# power_dist.net
KiCad netlist of a schematic drawn in EAGLE
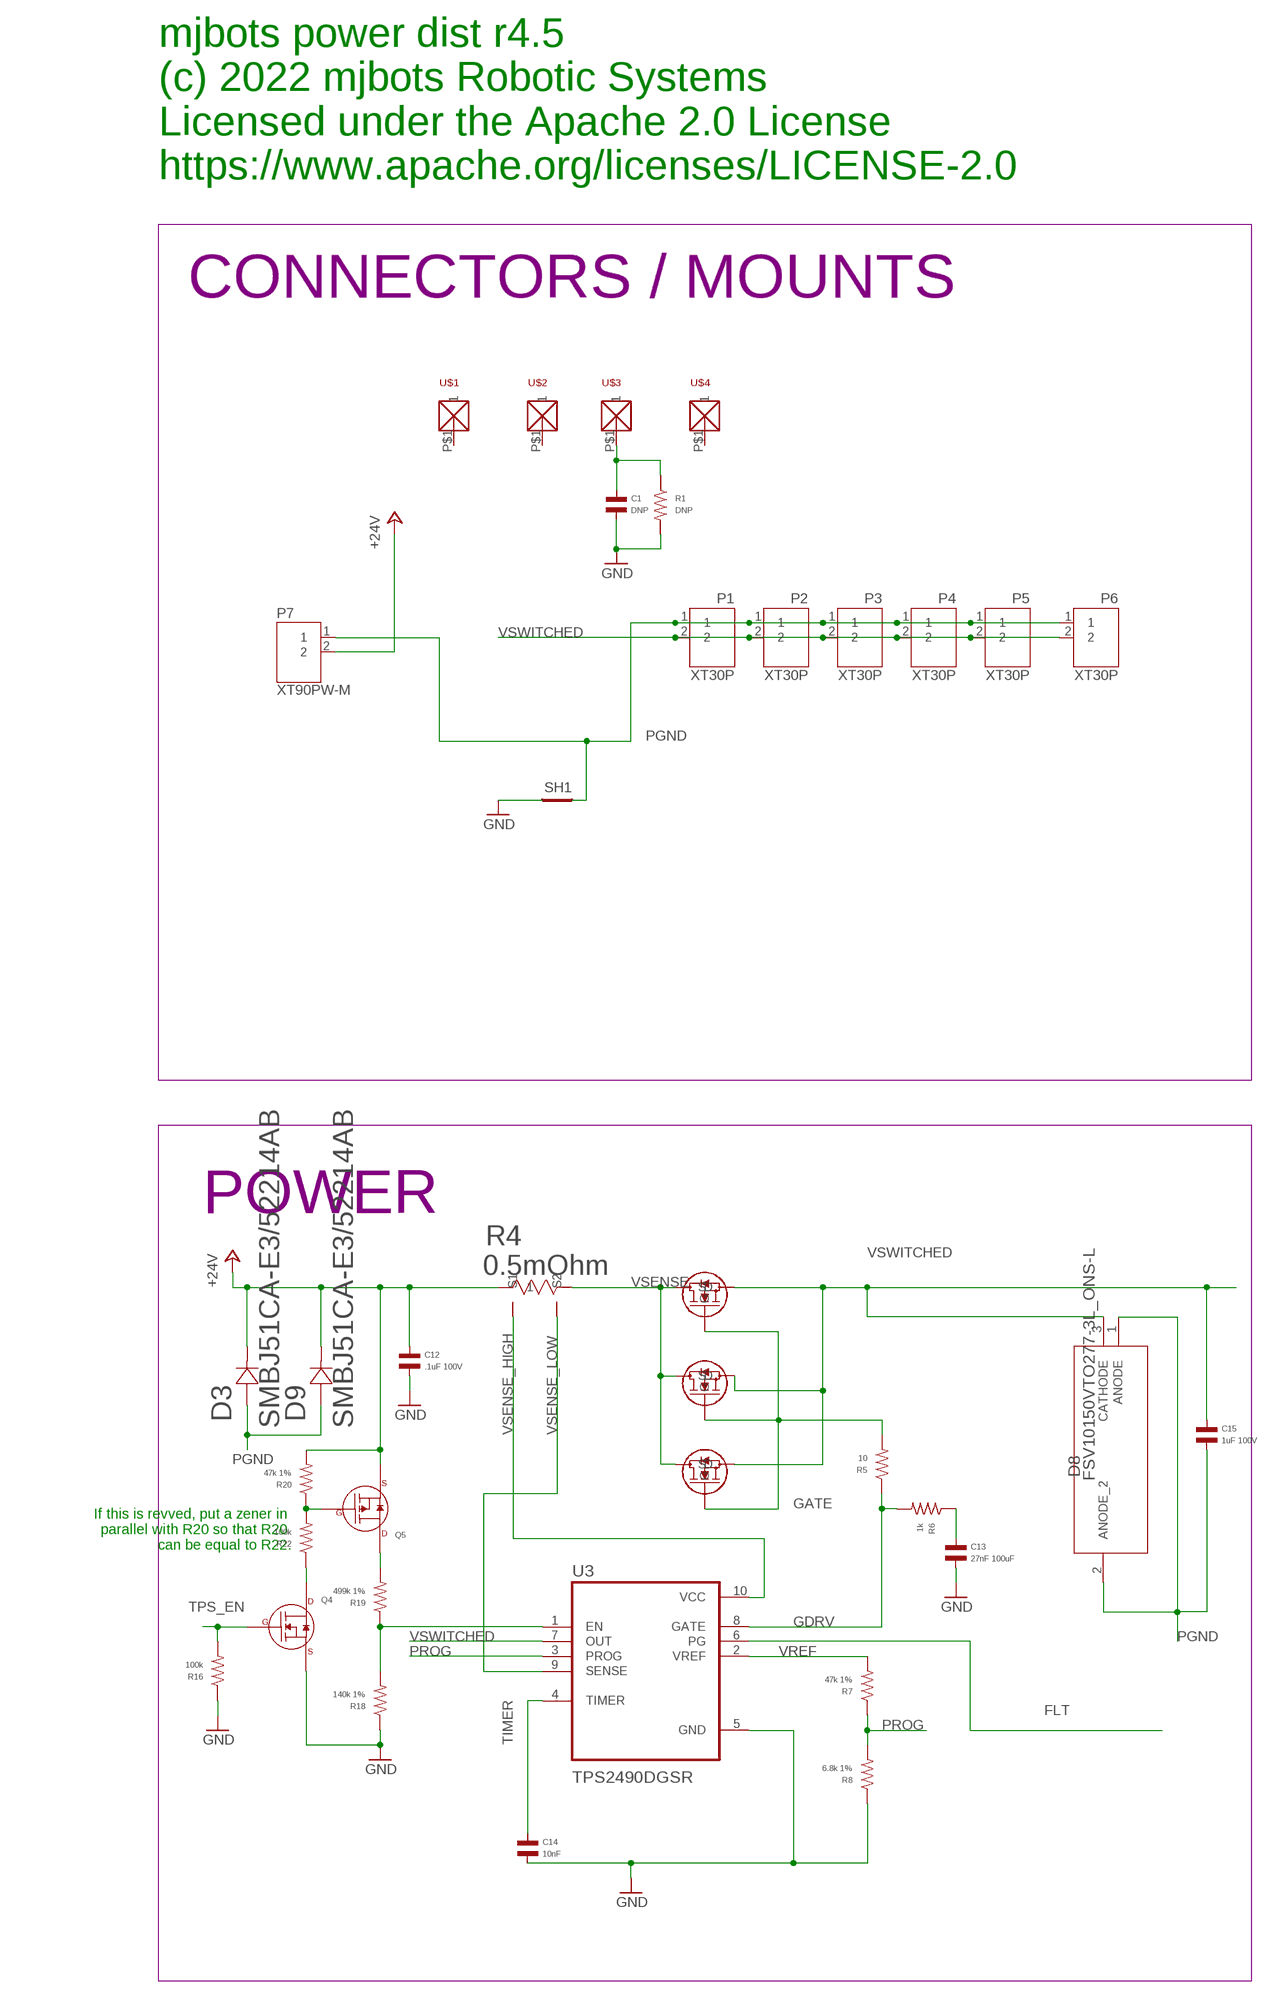
[diagram p0: schematic, sheet 1, part 1 of 2]
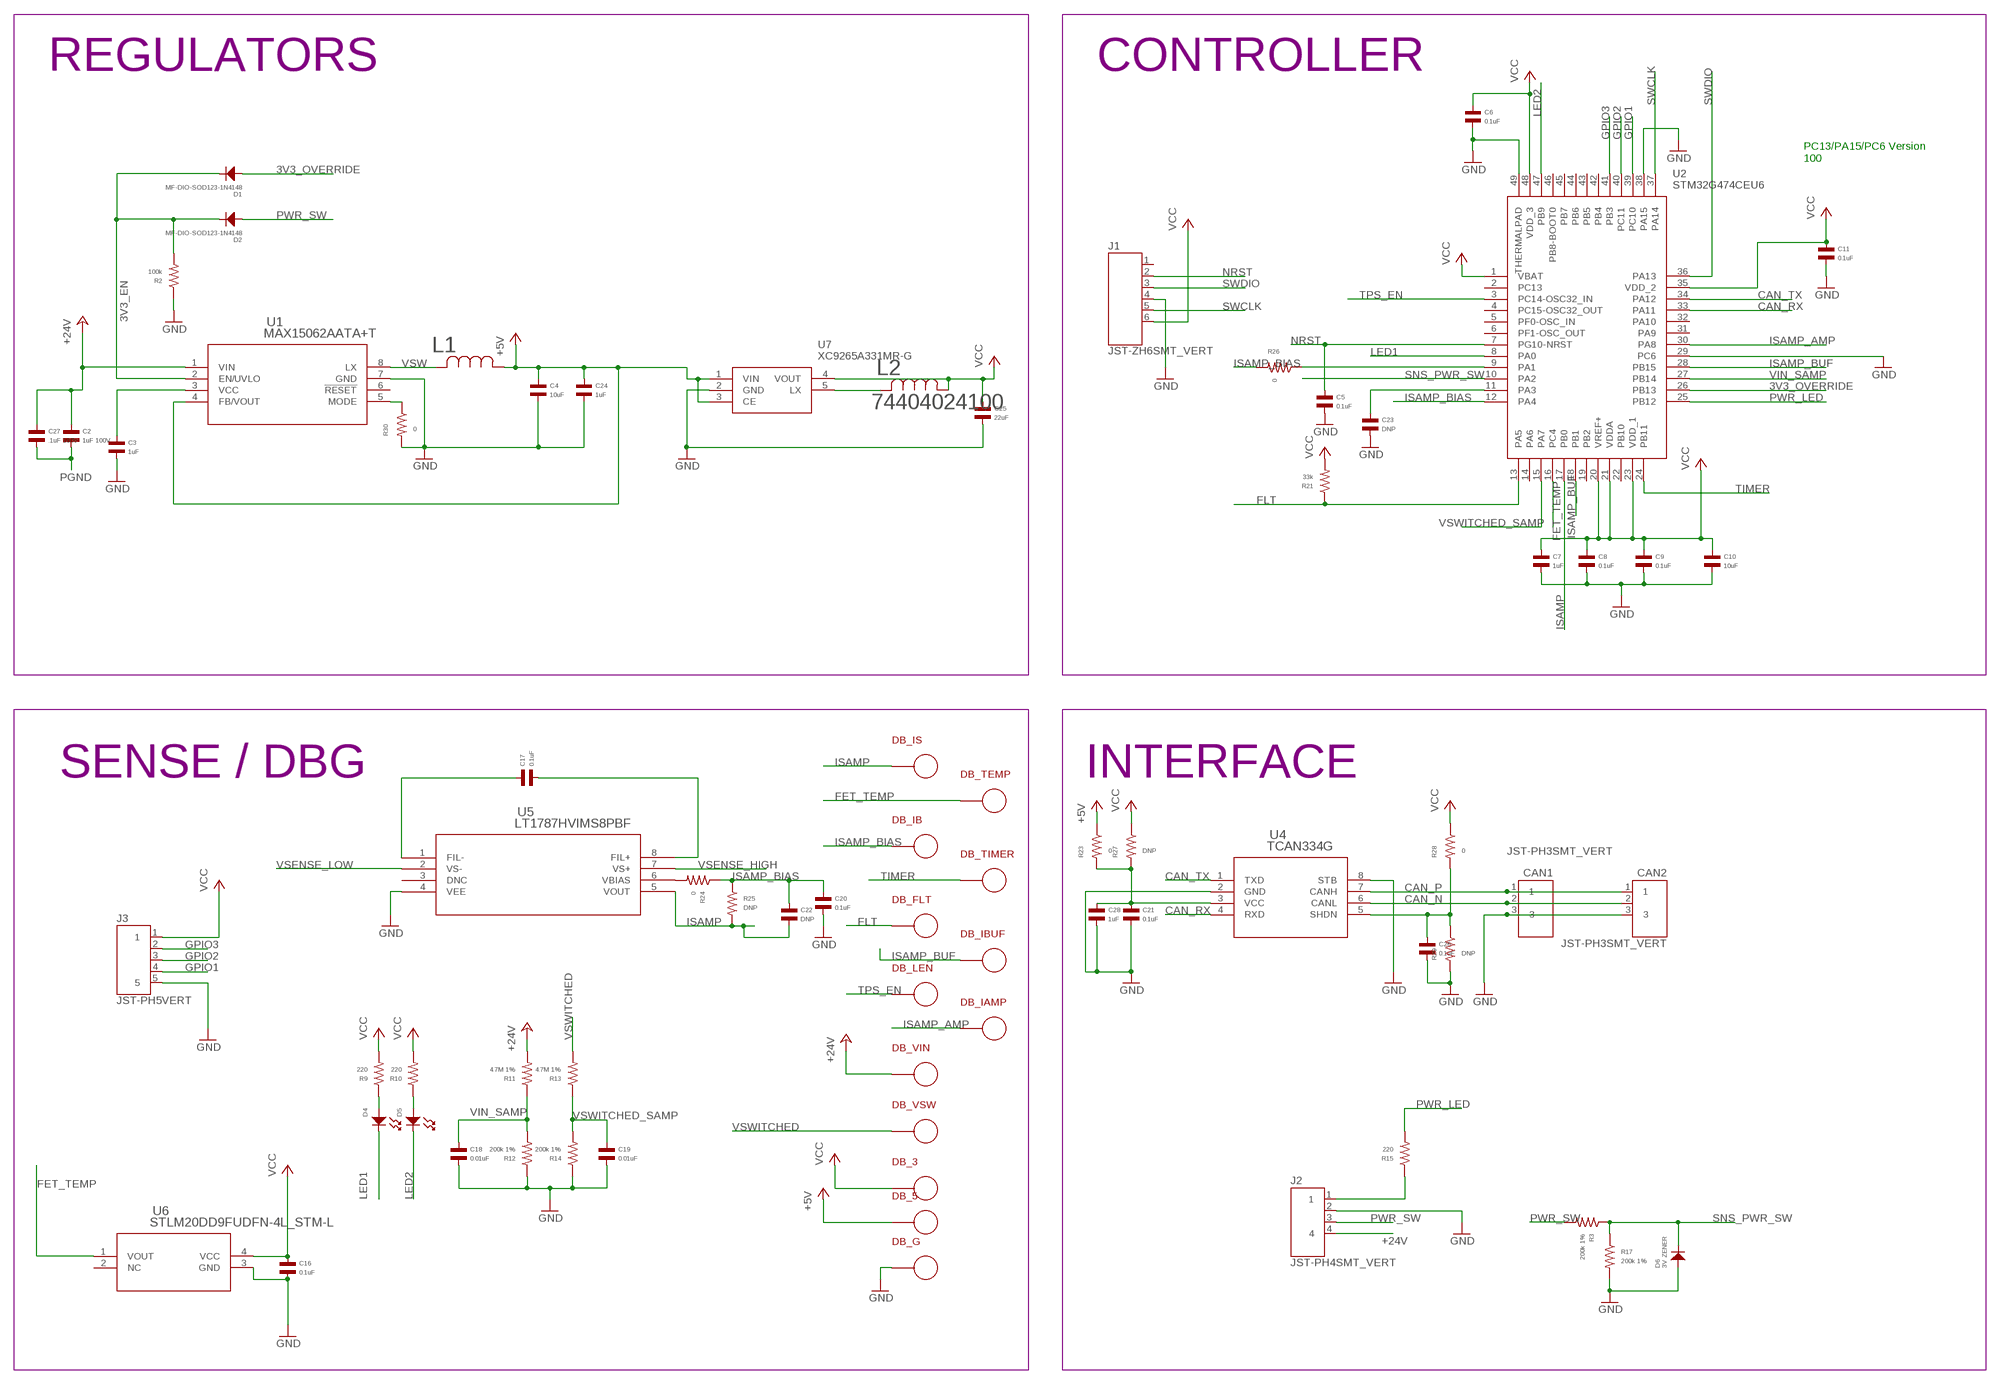
[diagram p1: schematic, sheet 1, part 2 of 2]

(export (version "E")
  (design (tool "Eeschema 10.0.6"))
  (components
    (comp (ref "C1")
      (value "DNP")
      (footprint "eagle-import:C0603")
      (fields (field (name "POPULATE") "0"))
      (libsource (lib "eagle-import") (part "CAPACITOR_NP_0603"))
    )
    (comp (ref "C2")
      (value "1uF 100V")
      (footprint "eagle-import:C0805")
      (fields (field (name "MF") "MURATA") (field (name "MPN") "GCM21BC72A105KE36L"))
      (libsource (lib "eagle-import") (part "CAPACITOR_NP_0805"))
    )
    (comp (ref "C3")
      (value "1uF")
      (footprint "eagle-import:C0603")
      (fields (field (name "HOUSEPART") "1") (field (name "MPN") "MF-CAP-0603-1uF"))
      (libsource (lib "eagle-import") (part "CAPACITOR_NP_0603"))
    )
    (comp (ref "C4")
      (value "10uF")
      (footprint "eagle-import:C1206")
      (fields (field (name "HOUSEPART") "1") (field (name "MPN") "MF-CAP-1206-10uF"))
      (libsource (lib "eagle-import") (part "CAPACITOR_NP_1206"))
    )
    (comp (ref "C5")
      (value "0.1uF")
      (footprint "eagle-import:C0603")
      (fields (field (name "HOUSEPART") "1") (field (name "MPN") "MF-CAP-0603-0.1uF"))
      (libsource (lib "eagle-import") (part "CAPACITOR_NP_0603"))
    )
    (comp (ref "C6")
      (value "0.1uF")
      (footprint "eagle-import:C0603")
      (fields (field (name "HOUSEPART") "1") (field (name "MPN") "MF-CAP-0603-0.1uF"))
      (libsource (lib "eagle-import") (part "CAPACITOR_NP_0603"))
    )
    (comp (ref "C7")
      (value "1uF")
      (footprint "eagle-import:C0603")
      (fields (field (name "HOUSEPART") "1") (field (name "MPN") "MF-CAP-0603-1uF"))
      (libsource (lib "eagle-import") (part "CAPACITOR_NP_0603"))
    )
    (comp (ref "C8")
      (value "0.1uF")
      (footprint "eagle-import:C0603")
      (fields (field (name "HOUSEPART") "1") (field (name "MPN") "MF-CAP-0603-0.1uF"))
      (libsource (lib "eagle-import") (part "CAPACITOR_NP_0603"))
    )
    (comp (ref "C9")
      (value "0.1uF")
      (footprint "eagle-import:C0603")
      (fields (field (name "HOUSEPART") "1") (field (name "MPN") "MF-CAP-0603-0.1uF"))
      (libsource (lib "eagle-import") (part "CAPACITOR_NP_0603"))
    )
    (comp (ref "C10")
      (value "10uF")
      (footprint "eagle-import:C1206")
      (fields (field (name "HOUSEPART") "1") (field (name "MPN") "MF-CAP-1206-10uF"))
      (libsource (lib "eagle-import") (part "CAPACITOR_NP_1206"))
    )
    (comp (ref "C11")
      (value "0.1uF")
      (footprint "eagle-import:C0603")
      (fields (field (name "HOUSEPART") "1") (field (name "MPN") "MF-CAP-0603-0.1uF"))
      (libsource (lib "eagle-import") (part "CAPACITOR_NP_0603"))
    )
    (comp (ref "C12")
      (value ".1uF 100V")
      (footprint "eagle-import:C0603")
      (fields (field (name "HOUSEPART") "0") (field (name "MPN") "GRM188R72A104KA35D"))
      (libsource (lib "eagle-import") (part "CAPACITOR_NP_0603"))
    )
    (comp (ref "C13")
      (value "27nF 100uF")
      (footprint "eagle-import:C0603")
      (fields (field (name "HOUSEPART") "0") (field (name "MPN") "C0603C273K1RAC7867"))
      (libsource (lib "eagle-import") (part "CAPACITOR_NP_0603"))
    )
    (comp (ref "C14")
      (value "10nF")
      (footprint "eagle-import:C0603")
      (fields (field (name "HOUSEPART") "1") (field (name "MPN") "MF-CAP-0603-0.01uF"))
      (libsource (lib "eagle-import") (part "CAPACITOR_NP_0603"))
    )
    (comp (ref "C15")
      (value "1uF 100V")
      (footprint "eagle-import:C0805")
      (fields (field (name "MF") "MURATA") (field (name "MPN") "GCM21BC72A105KE36L"))
      (libsource (lib "eagle-import") (part "CAPACITOR_NP_0805"))
    )
    (comp (ref "C16")
      (value "0.1uF")
      (footprint "eagle-import:C0603")
      (fields (field (name "HOUSEPART") "1") (field (name "MPN") "MF-CAP-0603-0.1uF"))
      (libsource (lib "eagle-import") (part "CAPACITOR_NP_0603"))
    )
    (comp (ref "C17")
      (value "0.1uF")
      (footprint "eagle-import:C0603")
      (fields (field (name "HOUSEPART") "1") (field (name "MPN") "MF-CAP-0603-0.1uF"))
      (libsource (lib "eagle-import") (part "CAPACITOR_NP_0603"))
    )
    (comp (ref "C18")
      (value "0.01uF")
      (footprint "eagle-import:C0603")
      (fields (field (name "HOUSEPART") "1") (field (name "MPN") "MF-CAP-0603-0.01uF"))
      (libsource (lib "eagle-import") (part "CAPACITOR_NP_0603"))
    )
    (comp (ref "C19")
      (value "0.01uF")
      (footprint "eagle-import:C0603")
      (fields (field (name "HOUSEPART") "1") (field (name "MPN") "MF-CAP-0603-0.01uF"))
      (libsource (lib "eagle-import") (part "CAPACITOR_NP_0603"))
    )
    (comp (ref "C20")
      (value "0.1uF")
      (footprint "eagle-import:C0603")
      (fields (field (name "HOUSEPART") "1") (field (name "MPN") "MF-CAP-0603-0.1uF"))
      (libsource (lib "eagle-import") (part "CAPACITOR_NP_0603"))
    )
    (comp (ref "C21")
      (value "0.1uF")
      (footprint "eagle-import:C0603")
      (fields (field (name "HOUSEPART") "1") (field (name "MPN") "MF-CAP-0603-0.1uF"))
      (libsource (lib "eagle-import") (part "CAPACITOR_NP_0603"))
    )
    (comp (ref "C22")
      (value "DNP")
      (footprint "eagle-import:C0603")
      (fields (field (name "HOUSEPART") "1") (field (name "POPULATE") "0"))
      (libsource (lib "eagle-import") (part "CAPACITOR_NP_0603"))
    )
    (comp (ref "C23")
      (value "DNP")
      (footprint "eagle-import:C0603")
      (fields (field (name "HOUSEPART") "1") (field (name "POPULATE") "0"))
      (libsource (lib "eagle-import") (part "CAPACITOR_NP_0603"))
    )
    (comp (ref "C24")
      (value "1uF")
      (footprint "eagle-import:C0402")
      (fields (field (name "HOUSEPART") "1") (field (name "MPN") "MF-CAP-0402-1uF"))
      (libsource (lib "eagle-import") (part "CAPACITOR_NP_0402"))
    )
    (comp (ref "C25")
      (value "22uF")
      (footprint "eagle-import:C1206")
      (fields (field (name "MF") "Samsung") (field (name "MPN") "CL31B226KPHNNNE"))
      (libsource (lib "eagle-import") (part "CAPACITOR_NP_1206"))
    )
    (comp (ref "C26")
      (value "0.1uF")
      (footprint "eagle-import:C0603")
      (fields (field (name "HOUSEPART") "1") (field (name "MPN") "MF-CAP-0603-0.1uF"))
      (libsource (lib "eagle-import") (part "CAPACITOR_NP_0603"))
    )
    (comp (ref "C27")
      (value ".1uF 100V")
      (footprint "eagle-import:C0603")
      (fields (field (name "HOUSEPART") "0") (field (name "MPN") "GRM188R72A104KA35D"))
      (libsource (lib "eagle-import") (part "CAPACITOR_NP_0603"))
    )
    (comp (ref "C28")
      (value "1uF")
      (footprint "eagle-import:C0603")
      (fields (field (name "HOUSEPART") "1") (field (name "MPN") "MF-CAP-0603-1uF"))
      (libsource (lib "eagle-import") (part "CAPACITOR_NP_0603"))
    )
    (comp (ref "CAN1")
      (value "JST-PH3SMT_VERT")
      (footprint "eagle-import:JST_B3B_PH-SM4-TB(LF)(SN)")
      (fields (field (name "MF") "JST") (field (name "MPN") "B3B-PH-SM4-TB(LF)(SN)"))
      (libsource (lib "eagle-import") (part "JST-PH3SMT_VERT"))
    )
    (comp (ref "CAN2")
      (value "JST-PH3SMT_VERT")
      (footprint "eagle-import:JST_B3B_PH-SM4-TB(LF)(SN)")
      (fields (field (name "MF") "JST") (field (name "MPN") "B3B-PH-SM4-TB(LF)(SN)"))
      (libsource (lib "eagle-import") (part "JST-PH3SMT_VERT"))
    )
    (comp (ref "D1")
      (value "MF-DIO-SOD123-1N4148")
      (footprint "eagle-import:SOD-123")
      (fields (field (name "HOUSEPART") "YES"))
      (libsource (lib "eagle-import") (part "DIODES_SOD-123_1N4148"))
    )
    (comp (ref "D2")
      (value "MF-DIO-SOD123-1N4148")
      (footprint "eagle-import:SOD-123")
      (fields (field (name "HOUSEPART") "YES"))
      (libsource (lib "eagle-import") (part "DIODES_SOD-123_1N4148"))
    )
    (comp (ref "D3")
      (value "SMBJ51CA-E3/52214AB")
      (footprint "eagle-import:DIODE_DO-214AB")
      (fields (field (name "MPN") "SMC5K51A-M3/I"))
      (libsource (lib "eagle-import") (part "SMBJ51CA-E3/52214AB"))
    )
    (comp (ref "D4")
      (value "LED_SINGLE-0603")
      (footprint "eagle-import:LED0603")
      (fields
        (field (name "HOUSEPART") "NO")
        (field (name "HOUSEPART_1") "1")
        (field (name "MPN") "MF-LED-0603-RED")
      )
      (libsource (lib "eagle-import") (part "LED_SINGLE-0603"))
    )
    (comp (ref "D5")
      (value "LED_SINGLE-0603")
      (footprint "eagle-import:LED0603")
      (fields
        (field (name "HOUSEPART") "NO")
        (field (name "HOUSEPART_1") "1")
        (field (name "MPN") "MF-LED-0603-RED")
      )
      (libsource (lib "eagle-import") (part "LED_SINGLE-0603"))
    )
    (comp (ref "D6")
      (value "3V ZENER")
      (footprint "eagle-import:SOD-123")
      (fields
        (field (name "HOUSEPART") "YES")
        (field (name "MPN") "MF-DIO-SOD123-1N4148")
        (field (name "MPN_1") "MMSZ4682T1G")
      )
      (libsource (lib "eagle-import") (part "DIODES_SOD-123_1N4148"))
    )
    (comp (ref "D8")
      (value "FSV10150VTO277-3L_ONS-L")
      (footprint "eagle-import:TO277-3L_ONS-L")
      (fields
        (field (name "MANUFACTURER_PART_NUMBER") "FSV10150V")
        (field (name "COPYRIGHT") "Copyright (C) 2018 Accelerated Designs. All rights reserved")
      )
      (libsource (lib "eagle-import") (part "FSV10150VTO277-3L_ONS-L"))
    )
    (comp (ref "D9")
      (value "SMBJ51CA-E3/52214AB")
      (footprint "eagle-import:DIODE_DO-214AB")
      (fields (field (name "MPN") "SMC5K51A-M3/I"))
      (libsource (lib "eagle-import") (part "SMBJ51CA-E3/52214AB"))
    )
    (comp (ref "DB_3")
      (value "PAD24AWG_PAD")
      (footprint "eagle-import:24AWG_PAD")
      (libsource (lib "eagle-import") (part "PAD24AWG_PAD"))
    )
    (comp (ref "DB_5")
      (value "PAD24AWG_PAD")
      (footprint "eagle-import:24AWG_PAD")
      (libsource (lib "eagle-import") (part "PAD24AWG_PAD"))
    )
    (comp (ref "DB_FLT")
      (value "PAD24AWG_PAD")
      (footprint "eagle-import:24AWG_PAD")
      (libsource (lib "eagle-import") (part "PAD24AWG_PAD"))
    )
    (comp (ref "DB_G")
      (value "PAD24AWG_PAD")
      (footprint "eagle-import:24AWG_PAD")
      (libsource (lib "eagle-import") (part "PAD24AWG_PAD"))
    )
    (comp (ref "DB_IAMP")
      (value "PAD24AWG_PAD")
      (footprint "eagle-import:24AWG_PAD")
      (libsource (lib "eagle-import") (part "PAD24AWG_PAD"))
    )
    (comp (ref "DB_IB")
      (value "PAD24AWG_PAD")
      (footprint "eagle-import:24AWG_PAD")
      (libsource (lib "eagle-import") (part "PAD24AWG_PAD"))
    )
    (comp (ref "DB_IBUF")
      (value "PAD24AWG_PAD")
      (footprint "eagle-import:24AWG_PAD")
      (libsource (lib "eagle-import") (part "PAD24AWG_PAD"))
    )
    (comp (ref "DB_IS")
      (value "PAD24AWG_PAD")
      (footprint "eagle-import:24AWG_PAD")
      (libsource (lib "eagle-import") (part "PAD24AWG_PAD"))
    )
    (comp (ref "DB_LEN")
      (value "PAD24AWG_PAD")
      (footprint "eagle-import:24AWG_PAD")
      (libsource (lib "eagle-import") (part "PAD24AWG_PAD"))
    )
    (comp (ref "DB_TEMP")
      (value "PAD24AWG_PAD")
      (footprint "eagle-import:24AWG_PAD")
      (libsource (lib "eagle-import") (part "PAD24AWG_PAD"))
    )
    (comp (ref "DB_TIMER")
      (value "PAD24AWG_PAD")
      (footprint "eagle-import:24AWG_PAD")
      (libsource (lib "eagle-import") (part "PAD24AWG_PAD"))
    )
    (comp (ref "DB_VIN")
      (value "PAD24AWG_PAD")
      (footprint "eagle-import:24AWG_PAD")
      (libsource (lib "eagle-import") (part "PAD24AWG_PAD"))
    )
    (comp (ref "DB_VSW")
      (value "PAD24AWG_PAD")
      (footprint "eagle-import:24AWG_PAD")
      (libsource (lib "eagle-import") (part "PAD24AWG_PAD"))
    )
    (comp (ref "J1")
      (value "JST-ZH6SMT_VERT")
      (footprint "eagle-import:JST_B6B-ZR-SM4-TF(LF)(SN)")
      (fields (field (name "MF") "JST") (field (name "MPN") "B6B-ZR-SM4-TF(LF)(SN)"))
      (libsource (lib "eagle-import") (part "JST-ZH6SMT_VERT"))
    )
    (comp (ref "J2")
      (value "JST-PH4SMT_VERT")
      (footprint "eagle-import:JST_B4B_PH-SM4-TB(LF)(SN)")
      (fields (field (name "MF") "JST") (field (name "MPN") "B4B-PH-SM4-TB(LF)(SN)"))
      (libsource (lib "eagle-import") (part "JST-PH4SMT_VERT"))
    )
    (comp (ref "J3")
      (value "JST-PH5VERT")
      (footprint "eagle-import:JST_B5B_PH-SM4-TB(LF)(SN)")
      (fields (field (name "MF") "JST") (field (name "MPN") "B5B-PH-SM4-TB(LF)(SN)"))
      (libsource (lib "eagle-import") (part "JST-PH5VERT"))
    )
    (comp (ref "L1")
      (value "SRN4018-220M")
      (footprint "eagle-import:IND_BOURNS_SRN4018")
      (fields
        (field (name "MANUFACTURER_PART_NUMBER") "SRN4018220M")
        (field (name "MANUFACTURER_PART_NUMBER_1") "74404042470")
        (field (name "MF") "Wurth Electronics")
        (field (name "MPN") "74404042470")
        (field (name "VENDOR") "Wurth")
      )
      (libsource (lib "eagle-import") (part "SRN4018-220M"))
    )
    (comp (ref "L2")
      (value "74404024100")
      (footprint "eagle-import:IND_4024100_WRE")
      (fields
        (field (name "MF") "Wurth Electronics")
        (field (name "COPYRIGHT") "Copyright (C) 2022 Ultra Librarian. All rights reserved.")
      )
      (libsource (lib "eagle-import") (part "74404024100"))
    )
    (comp (ref "P1")
      (value "XT30P")
      (footprint "eagle-import:XT30P")
      (fields (field (name "MF") "AMASS") (field (name "MPN") "XT30UPB-F"))
      (libsource (lib "eagle-import") (part "XT30P"))
    )
    (comp (ref "P2")
      (value "XT30P")
      (footprint "eagle-import:XT30P")
      (fields (field (name "MF") "AMASS") (field (name "MPN") "XT30UPB-F"))
      (libsource (lib "eagle-import") (part "XT30P"))
    )
    (comp (ref "P3")
      (value "XT30P")
      (footprint "eagle-import:XT30P")
      (fields (field (name "MF") "AMASS") (field (name "MPN") "XT30UPB-F"))
      (libsource (lib "eagle-import") (part "XT30P"))
    )
    (comp (ref "P4")
      (value "XT30P")
      (footprint "eagle-import:XT30P")
      (fields (field (name "MF") "AMASS") (field (name "MPN") "XT30UPB-F"))
      (libsource (lib "eagle-import") (part "XT30P"))
    )
    (comp (ref "P5")
      (value "XT30P")
      (footprint "eagle-import:XT30P")
      (fields (field (name "MF") "AMASS") (field (name "MPN") "XT30UPB-F"))
      (libsource (lib "eagle-import") (part "XT30P"))
    )
    (comp (ref "P6")
      (value "XT30P")
      (footprint "eagle-import:XT30P")
      (fields (field (name "MF") "AMASS") (field (name "MPN") "XT30UPB-F"))
      (libsource (lib "eagle-import") (part "XT30P"))
    )
    (comp (ref "P7")
      (value "XT90PW-M")
      (footprint "eagle-import:XT90PW-M")
      (libsource (lib "eagle-import") (part "XT90PW-M"))
    )
    (comp (ref "Q1")
      (value "PSMN4R8-100BSEJ")
      (footprint "eagle-import:D2PAK_SOT404_NEX")
      (fields
        (field (name "MANUFACTURER_PART_NUMBER") "PSMN3R7-100BSE")
        (field (name "MPN") "PSMN3R7-100BSE")
        (field (name "COPYRIGHT") "Copyright (C) 2018 Accelerated Designs. All rights reserved")
      )
      (libsource (lib "eagle-import") (part "PSMN4R8-100BSEJ"))
    )
    (comp (ref "Q2")
      (value "PSMN4R8-100BSEJ")
      (footprint "eagle-import:D2PAK_SOT404_NEX")
      (fields
        (field (name "MANUFACTURER_PART_NUMBER") "PSMN3R7-100BSE")
        (field (name "MPN") "PSMN3R7-100BSE")
        (field (name "COPYRIGHT") "Copyright (C) 2018 Accelerated Designs. All rights reserved")
      )
      (libsource (lib "eagle-import") (part "PSMN4R8-100BSEJ"))
    )
    (comp (ref "Q3")
      (value "PSMN4R8-100BSEJ")
      (footprint "eagle-import:D2PAK_SOT404_NEX")
      (fields
        (field (name "MANUFACTURER_PART_NUMBER") "PSMN3R7-100BSE")
        (field (name "MPN") "PSMN3R7-100BSE")
        (field (name "COPYRIGHT") "Copyright (C) 2018 Accelerated Designs. All rights reserved")
      )
      (libsource (lib "eagle-import") (part "PSMN4R8-100BSEJ"))
    )
    (comp (ref "Q4")
      (value "N-CHANNEL_FET_SOT-23-3")
      (footprint "eagle-import:SOT-23-3")
      (fields (field (name "HOUSEPART") "NO") (field (name "MPN") "BSS123"))
      (libsource (lib "eagle-import") (part "N-CHANNEL_FET_SOT-23-3"))
    )
    (comp (ref "Q5")
      (value "P-CHANNEL_FET_SOT-23-3")
      (footprint "eagle-import:SOT-23-3")
      (fields (field (name "HOUSEPART") "NO") (field (name "MPN") "ZXMP10A13FTA"))
      (libsource (lib "eagle-import") (part "P-CHANNEL_FET_SOT-23-3"))
    )
    (comp (ref "R1")
      (value "DNP")
      (footprint "eagle-import:R0603")
      (fields (field (name "POPULATE") "0"))
      (libsource (lib "eagle-import") (part "RESISTOR_0603"))
    )
    (comp (ref "R2")
      (value "100k")
      (footprint "eagle-import:R0603")
      (fields (field (name "HOUSEPART") "1") (field (name "MPN") "MF-RES-0603-100K"))
      (libsource (lib "eagle-import") (part "RESISTOR_0603"))
    )
    (comp (ref "R3")
      (value "200k 1%")
      (footprint "eagle-import:R0603")
      (fields (field (name "HOUSEPART") "0") (field (name "MPN") "RC0603FR-07200KL"))
      (libsource (lib "eagle-import") (part "RESISTOR_0603"))
    )
    (comp (ref "R4")
      (value "0.5mOhm")
      (footprint "eagle-import:SHUNT2512")
      (fields (field (name "MF") "VISHAY DALE") (field (name "MPN") "WSLF2512L5000FEA"))
      (libsource (lib "eagle-import") (part "SENSE_RESISTOR2512"))
    )
    (comp (ref "R5")
      (value "10")
      (footprint "eagle-import:R0603")
      (fields (field (name "HOUSEPART") "1") (field (name "MPN") "MF-RES-0603-10"))
      (libsource (lib "eagle-import") (part "RESISTOR_0603"))
    )
    (comp (ref "R6")
      (value "1k")
      (footprint "eagle-import:R0603")
      (fields (field (name "HOUSEPART") "1") (field (name "MPN") "MF-RES-0603-1K"))
      (libsource (lib "eagle-import") (part "RESISTOR_0603"))
    )
    (comp (ref "R7")
      (value "47k 1%")
      (footprint "eagle-import:R0603")
      (fields (field (name "HOUSEPART") "0") (field (name "MPN") "RC0603FR-0747KL"))
      (libsource (lib "eagle-import") (part "RESISTOR_0603"))
    )
    (comp (ref "R8")
      (value "6.8k 1%")
      (footprint "eagle-import:R0603")
      (fields (field (name "HOUSEPART") "0") (field (name "MPN") "RC0603FR-076K8L"))
      (libsource (lib "eagle-import") (part "RESISTOR_0603"))
    )
    (comp (ref "R9")
      (value "220")
      (footprint "eagle-import:R0603")
      (fields (field (name "HOUSEPART") "1") (field (name "MPN") "MF-RES-0603-220"))
      (libsource (lib "eagle-import") (part "RESISTOR_0603"))
    )
    (comp (ref "R10")
      (value "220")
      (footprint "eagle-import:R0603")
      (fields (field (name "HOUSEPART") "1") (field (name "MPN") "MF-RES-0603-220"))
      (libsource (lib "eagle-import") (part "RESISTOR_0603"))
    )
    (comp (ref "R11")
      (value "4.7M 1%")
      (footprint "eagle-import:R0603")
      (fields (field (name "HOUSEPART") "0") (field (name "MPN") "RC0603FR-074M7L"))
      (libsource (lib "eagle-import") (part "RESISTOR_0603"))
    )
    (comp (ref "R12")
      (value "200k 1%")
      (footprint "eagle-import:R0603")
      (fields (field (name "HOUSEPART") "0") (field (name "MPN") "RC0603FR-07200KL"))
      (libsource (lib "eagle-import") (part "RESISTOR_0603"))
    )
    (comp (ref "R13")
      (value "4.7M 1%")
      (footprint "eagle-import:R0603")
      (fields (field (name "HOUSEPART") "0") (field (name "MPN") "RC0603FR-074M7L"))
      (libsource (lib "eagle-import") (part "RESISTOR_0603"))
    )
    (comp (ref "R14")
      (value "200k 1%")
      (footprint "eagle-import:R0603")
      (fields (field (name "HOUSEPART") "0") (field (name "MPN") "RC0603FR-07200KL"))
      (libsource (lib "eagle-import") (part "RESISTOR_0603"))
    )
    (comp (ref "R15")
      (value "220")
      (footprint "eagle-import:R0603")
      (fields (field (name "HOUSEPART") "1") (field (name "MPN") "MF-RES-0603-220"))
      (libsource (lib "eagle-import") (part "RESISTOR_0603"))
    )
    (comp (ref "R16")
      (value "100k")
      (footprint "eagle-import:R0603")
      (fields (field (name "HOUSEPART") "1") (field (name "MPN") "MF-RES-0603-100K"))
      (libsource (lib "eagle-import") (part "RESISTOR_0603"))
    )
    (comp (ref "R17")
      (value "200k 1%")
      (footprint "eagle-import:R0603")
      (fields (field (name "HOUSEPART") "0") (field (name "MPN") "RC0603FR-07200KL"))
      (libsource (lib "eagle-import") (part "RESISTOR_0603"))
    )
    (comp (ref "R18")
      (value "140k 1%")
      (footprint "eagle-import:R0603")
      (fields (field (name "HOUSEPART") "0") (field (name "MPN") "RC0603FR-07140KL"))
      (libsource (lib "eagle-import") (part "RESISTOR_0603"))
    )
    (comp (ref "R19")
      (value "499k 1%")
      (footprint "eagle-import:R0603")
      (fields (field (name "HOUSEPART") "0") (field (name "MPN") "RC0603FR-07499KL"))
      (libsource (lib "eagle-import") (part "RESISTOR_0603"))
    )
    (comp (ref "R20")
      (value "47k 1%")
      (footprint "eagle-import:R0603")
      (fields (field (name "HOUSEPART") "0") (field (name "MPN") "RC0603FR-0747KL"))
      (libsource (lib "eagle-import") (part "RESISTOR_0603"))
    )
    (comp (ref "R21")
      (value "33k")
      (footprint "eagle-import:R0603")
      (fields (field (name "HOUSEPART") "1") (field (name "MPN") "RC0603FR-0733KL"))
      (libsource (lib "eagle-import") (part "RESISTOR_0603"))
    )
    (comp (ref "R22")
      (value "100k")
      (footprint "eagle-import:R0603")
      (fields (field (name "HOUSEPART") "1") (field (name "MPN") "MF-RES-0603-100K"))
      (libsource (lib "eagle-import") (part "RESISTOR_0603"))
    )
    (comp (ref "R23")
      (value "0")
      (footprint "eagle-import:R0603")
      (fields (field (name "HOUSEPART") "1") (field (name "MPN") "MF-RES-0603-0"))
      (libsource (lib "eagle-import") (part "RESISTOR_0603"))
    )
    (comp (ref "R24")
      (value "0")
      (footprint "eagle-import:R0603")
      (fields (field (name "HOUSEPART") "1") (field (name "MPN") "MF-RES-0603-0"))
      (libsource (lib "eagle-import") (part "RESISTOR_0603"))
    )
    (comp (ref "R25")
      (value "DNP")
      (footprint "eagle-import:R0603")
      (fields (field (name "HOUSEPART") "1") (field (name "POPULATE") "0"))
      (libsource (lib "eagle-import") (part "RESISTOR_0603"))
    )
    (comp (ref "R26")
      (value "0")
      (footprint "eagle-import:R0603")
      (fields (field (name "HOUSEPART") "1") (field (name "MPN") "MF-RES-0603-0"))
      (libsource (lib "eagle-import") (part "RESISTOR_0603"))
    )
    (comp (ref "R27")
      (value "DNP")
      (footprint "eagle-import:R0603")
      (fields
        (field (name "HOUSEPART") "1")
        (field (name "MPN") "MF-RES-0603-0")
        (field (name "POPULATE") "0")
      )
      (libsource (lib "eagle-import") (part "RESISTOR_0603"))
    )
    (comp (ref "R28")
      (value "0")
      (footprint "eagle-import:R0603")
      (fields (field (name "HOUSEPART") "1") (field (name "MPN") "MF-RES-0603-0"))
      (libsource (lib "eagle-import") (part "RESISTOR_0603"))
    )
    (comp (ref "R29")
      (value "DNP")
      (footprint "eagle-import:R0603")
      (fields
        (field (name "HOUSEPART") "1")
        (field (name "MPN") "MF-RES-0603-0")
        (field (name "POPULATE") "0")
      )
      (libsource (lib "eagle-import") (part "RESISTOR_0603"))
    )
    (comp (ref "R30")
      (value "0")
      (footprint "eagle-import:R0603")
      (fields (field (name "HOUSEPART") "1") (field (name "MPN") "MF-RES-0603-0"))
      (libsource (lib "eagle-import") (part "RESISTOR_0603"))
    )
    (comp (ref "SH1")
      (value "SHORTMEDIUM")
      (footprint "eagle-import:SHORT_TOP-MEDIUM")
      (libsource (lib "eagle-import") (part "SHORTMEDIUM"))
    )
    (comp (ref "U$1")
      (value "MOUNT")
      (footprint "eagle-import:M2.5MOUNT")
      (libsource (lib "eagle-import") (part "MOUNT"))
    )
    (comp (ref "U$2")
      (value "MOUNT")
      (footprint "eagle-import:M2.5MOUNT")
      (libsource (lib "eagle-import") (part "MOUNT"))
    )
    (comp (ref "U$3")
      (value "MOUNT")
      (footprint "eagle-import:M2.5MOUNT")
      (libsource (lib "eagle-import") (part "MOUNT"))
    )
    (comp (ref "U$4")
      (value "MOUNT")
      (footprint "eagle-import:M2.5MOUNT")
      (libsource (lib "eagle-import") (part "MOUNT"))
    )
    (comp (ref "U1")
      (value "MAX15062AATA+T")
      (footprint "eagle-import:21-0487A_MXM")
      (fields
        (field (name "MANUFACTURER_PART_NUMBER") "MAX15062BATA+T")
        (field (name "MF") "Maxim")
        (field (name "MPN") "MAX15062BATA+T")
        (field (name "COPYRIGHT") "Copyright (C) 2018 Accelerated Designs. All rights reserved")
      )
      (libsource (lib "eagle-import") (part "MAX15062AATA+T"))
    )
    (comp (ref "U2")
      (value "STM32G474CEU6")
      (footprint "eagle-import:QFN50P700X700X60-49N")
      (fields (field (name "MOUSER_PART_NUMBER") "511-STM32G474CEU6") (field (name "MF") "ST"))
      (libsource (lib "eagle-import") (part "STM32G474CEU6"))
    )
    (comp (ref "U3")
      (value "TPS2490DGSR")
      (footprint "eagle-import:SOP50P490X110-10N")
      (fields (field (name "DIGI-KEY_PART_NUMBER") "296-26924-1-ND") (field (name "MF") "Texas Instruments"))
      (libsource (lib "eagle-import") (part "TPS2490DGSR"))
    )
    (comp (ref "U4")
      (value "TCAN334G")
      (footprint "eagle-import:SOIC8")
      (fields (field (name "MF") "TI") (field (name "MPN") "TCAN1057AEVDRQ1"))
      (libsource (lib "eagle-import") (part "TCAN334G"))
    )
    (comp (ref "U5")
      (value "LT1787HVIMS8PBF")
      (footprint "eagle-import:MSOP-8_MS")
      (fields
        (field (name "DIGI-KEY_PART_NUMBER") "LT1787HVIMS8#PBF-ND")
        (field (name "MF") "Linear Technology")
        (field (name "MP") "LT1787HVIMS8#PBF")
      )
      (libsource (lib "eagle-import") (part "LT1787HVIMS8PBF"))
    )
    (comp (ref "U6")
      (value "STLM20DD9FUDFN-4L_STM-L")
      (footprint "eagle-import:UDFN-4L_STM-L")
      (fields
        (field (name "MANUFACTURER_PART_NUMBER") "STLM20DD9F")
        (field (name "COPYRIGHT") "Copyright (C) 2018 Accelerated Designs. All rights reserved")
      )
      (libsource (lib "eagle-import") (part "STLM20DD9FUDFN-4L_STM-L"))
    )
    (comp (ref "U7")
      (value "XC9265A331MR-G")
      (footprint "eagle-import:SOT95P280X130-5N")
      (fields (field (name "MOUSER_PART_NUMBER") "865-XC9265A331MR-G") (field (name "MF") "Torex"))
      (libsource (lib "eagle-import") (part "XC9265A331MR-G"))
    )
  )
  (nets
    (net (code "1") (name "+5V") (class "Default")
      (node (ref "C24") (pin "P$1") (pinfunction "P$1_P$1") (pintype "passive"))
      (node (ref "C4") (pin "P$1") (pinfunction "P$1_P$1") (pintype "passive"))
      (node (ref "DB_5") (pin "P$1") (pinfunction "P$1_P$1") (pintype "bidirectional"))
      (node (ref "L1") (pin "1") (pinfunction "1_1") (pintype "passive"))
      (node (ref "R23") (pin "P$1") (pinfunction "P$1_P$1") (pintype "passive"))
      (node (ref "U1") (pin "4") (pinfunction "FB/VOUT_4") (pintype "bidirectional"))
      (node (ref "U7") (pin "1") (pinfunction "VIN_1") (pintype "bidirectional"))
      (node (ref "U7") (pin "3") (pinfunction "CE_3") (pintype "bidirectional"))
    )
    (net (code "2") (name "+24V") (class "Default")
      (node (ref "C12") (pin "P$1") (pinfunction "P$1_P$1") (pintype "passive"))
      (node (ref "C2") (pin "P$1") (pinfunction "P$1_P$1") (pintype "passive"))
      (node (ref "C27") (pin "P$1") (pinfunction "P$1_P$1") (pintype "passive"))
      (node (ref "D3") (pin "P$1") (pinfunction "1_P$1") (pintype "passive"))
      (node (ref "D9") (pin "P$1") (pinfunction "1_P$1") (pintype "passive"))
      (node (ref "DB_VIN") (pin "P$1") (pinfunction "P$1_P$1") (pintype "bidirectional"))
      (node (ref "J2") (pin "4") (pinfunction "4_4") (pintype "passive"))
      (node (ref "P7") (pin "2") (pinfunction "2_2") (pintype "passive"))
      (node (ref "Q5") (pin "P$2") (pinfunction "SOURCE_P$2") (pintype "bidirectional"))
      (node (ref "R11") (pin "P$2") (pinfunction "P$2_P$2") (pintype "passive"))
      (node (ref "R20") (pin "P$2") (pinfunction "P$2_P$2") (pintype "passive"))
      (node (ref "R4") (pin "1") (pinfunction "1_1") (pintype "passive"))
      (node (ref "U1") (pin "1") (pinfunction "VIN_1") (pintype "input"))
    )
    (net (code "3") (name "/3V3_EN") (class "Default")
      (node (ref "D1") (pin "CATHODE") (pinfunction "CATHODE_CATHODE") (pintype "bidirectional"))
      (node (ref "D2") (pin "CATHODE") (pinfunction "CATHODE_CATHODE") (pintype "bidirectional"))
      (node (ref "R2") (pin "P$2") (pinfunction "P$2_P$2") (pintype "passive"))
      (node (ref "U1") (pin "2") (pinfunction "EN/UVLO_2") (pintype "input"))
    )
    (net (code "4") (name "/3V3_OVERRIDE") (class "Default")
      (node (ref "D1") (pin "ANODE") (pinfunction "ANODE_ANODE") (pintype "bidirectional"))
      (node (ref "U2") (pin "26") (pinfunction "PB13_26") (pintype "bidirectional"))
    )
    (net (code "5") (name "/CAN_N") (class "Default")
      (node (ref "CAN1") (pin "2") (pinfunction "2_2") (pintype "passive"))
      (node (ref "CAN2") (pin "2") (pinfunction "2_2") (pintype "passive"))
      (node (ref "U4") (pin "6") (pinfunction "CANL_6") (pintype "bidirectional"))
    )
    (net (code "6") (name "/CAN_P") (class "Default")
      (node (ref "CAN1") (pin "1") (pinfunction "1_1") (pintype "passive"))
      (node (ref "CAN2") (pin "1") (pinfunction "1_1") (pintype "passive"))
      (node (ref "U4") (pin "7") (pinfunction "CANH_7") (pintype "bidirectional"))
    )
    (net (code "7") (name "/CAN_RX") (class "Default")
      (node (ref "U2") (pin "33") (pinfunction "PA11_33") (pintype "bidirectional"))
      (node (ref "U4") (pin "4") (pinfunction "RXD_4") (pintype "output"))
    )
    (net (code "8") (name "/CAN_TX") (class "Default")
      (node (ref "U2") (pin "34") (pinfunction "PA12_34") (pintype "bidirectional"))
      (node (ref "U4") (pin "1") (pinfunction "TXD_1") (pintype "input"))
    )
    (net (code "9") (name "/FET_TEMP") (class "Default")
      (node (ref "DB_TEMP") (pin "P$1") (pinfunction "P$1_P$1") (pintype "bidirectional"))
      (node (ref "U2") (pin "16") (pinfunction "PC4_16") (pintype "bidirectional"))
      (node (ref "U6") (pin "1") (pinfunction "VOUT_1") (pintype "output"))
    )
    (net (code "10") (name "/FLT") (class "Default")
      (node (ref "DB_FLT") (pin "P$1") (pinfunction "P$1_P$1") (pintype "bidirectional"))
      (node (ref "R21") (pin "P$1") (pinfunction "P$1_P$1") (pintype "passive"))
      (node (ref "U2") (pin "13") (pinfunction "PA5_13") (pintype "bidirectional"))
      (node (ref "U3") (pin "6") (pinfunction "PG_6") (pintype "output"))
    )
    (net (code "11") (name "/GATE") (class "Default")
      (node (ref "Q1") (pin "1") (pinfunction "G_1") (pintype "passive"))
      (node (ref "Q2") (pin "1") (pinfunction "G_1") (pintype "passive"))
      (node (ref "Q3") (pin "1") (pinfunction "G_1") (pintype "passive"))
      (node (ref "R5") (pin "P$2") (pinfunction "P$2_P$2") (pintype "passive"))
    )
    (net (code "12") (name "/GDRV") (class "Default")
      (node (ref "R5") (pin "P$1") (pinfunction "P$1_P$1") (pintype "passive"))
      (node (ref "R6") (pin "P$2") (pinfunction "P$2_P$2") (pintype "passive"))
      (node (ref "U3") (pin "8") (pinfunction "GATE_8") (pintype "output"))
    )
    (net (code "13") (name "/GPIO1") (class "Default")
      (node (ref "J3") (pin "4") (pinfunction "4_4") (pintype "passive"))
      (node (ref "U2") (pin "39") (pinfunction "PC10_39") (pintype "bidirectional"))
    )
    (net (code "14") (name "/GPIO2") (class "Default")
      (node (ref "J3") (pin "3") (pinfunction "3_3") (pintype "passive"))
      (node (ref "U2") (pin "40") (pinfunction "PC11_40") (pintype "bidirectional"))
    )
    (net (code "15") (name "/GPIO3") (class "Default")
      (node (ref "J3") (pin "2") (pinfunction "2_2") (pintype "passive"))
      (node (ref "U2") (pin "41") (pinfunction "PB3_41") (pintype "bidirectional"))
    )
    (net (code "16") (name "/ISAMP") (class "Default")
      (node (ref "C22") (pin "P$2") (pinfunction "P$2_P$2") (pintype "passive"))
      (node (ref "DB_IS") (pin "P$1") (pinfunction "P$1_P$1") (pintype "bidirectional"))
      (node (ref "R25") (pin "P$2") (pinfunction "P$2_P$2") (pintype "passive"))
      (node (ref "U2") (pin "17") (pinfunction "PB0_17") (pintype "bidirectional"))
      (node (ref "U5") (pin "5") (pinfunction "VOUT_5") (pintype "output"))
    )
    (net (code "17") (name "/ISAMP_AMP") (class "Default")
      (node (ref "DB_IAMP") (pin "P$1") (pinfunction "P$1_P$1") (pintype "bidirectional"))
      (node (ref "U2") (pin "30") (pinfunction "PA8_30") (pintype "bidirectional"))
    )
    (net (code "18") (name "/ISAMP_BIAS") (class "Default")
      (node (ref "C20") (pin "P$1") (pinfunction "P$1_P$1") (pintype "passive"))
      (node (ref "C22") (pin "P$1") (pinfunction "P$1_P$1") (pintype "passive"))
      (node (ref "DB_IB") (pin "P$1") (pinfunction "P$1_P$1") (pintype "bidirectional"))
      (node (ref "R24") (pin "P$1") (pinfunction "P$1_P$1") (pintype "passive"))
      (node (ref "R25") (pin "P$1") (pinfunction "P$1_P$1") (pintype "passive"))
      (node (ref "R26") (pin "P$2") (pinfunction "P$2_P$2") (pintype "passive"))
      (node (ref "U2") (pin "12") (pinfunction "PA4_12") (pintype "bidirectional"))
    )
    (net (code "19") (name "/ISAMP_BUF") (class "Default")
      (node (ref "DB_IBUF") (pin "P$1") (pinfunction "P$1_P$1") (pintype "bidirectional"))
      (node (ref "U2") (pin "18") (pinfunction "PB1_18") (pintype "bidirectional"))
      (node (ref "U2") (pin "28") (pinfunction "PB15_28") (pintype "bidirectional"))
    )
    (net (code "20") (name "/LED1") (class "Default")
      (node (ref "D4") (pin "CATHODE") (pinfunction "CATHODE_CATHODE") (pintype "power_in"))
      (node (ref "U2") (pin "8") (pinfunction "PA0_8") (pintype "bidirectional"))
    )
    (net (code "21") (name "/LED2") (class "Default")
      (node (ref "D5") (pin "CATHODE") (pinfunction "CATHODE_CATHODE") (pintype "power_in"))
      (node (ref "U2") (pin "47") (pinfunction "PB9_47") (pintype "bidirectional"))
    )
    (net (code "22") (name "/NRST") (class "Default")
      (node (ref "C5") (pin "P$1") (pinfunction "P$1_P$1") (pintype "passive"))
      (node (ref "J1") (pin "2") (pinfunction "2_2") (pintype "passive"))
      (node (ref "U2") (pin "7") (pinfunction "PG10-NRST_7") (pintype "bidirectional"))
    )
    (net (code "23") (name "/PGND") (class "Default")
      (node (ref "C15") (pin "P$2") (pinfunction "P$2_P$2") (pintype "passive"))
      (node (ref "C2") (pin "P$2") (pinfunction "P$2_P$2") (pintype "passive"))
      (node (ref "C27") (pin "P$2") (pinfunction "P$2_P$2") (pintype "passive"))
      (node (ref "D3") (pin "P$2") (pinfunction "2_P$2") (pintype "passive"))
      (node (ref "D8") (pin "1") (pinfunction "ANODE_1") (pintype "passive"))
      (node (ref "D8") (pin "2") (pinfunction "ANODE_2_2") (pintype "passive"))
      (node (ref "D9") (pin "P$2") (pinfunction "2_P$2") (pintype "passive"))
      (node (ref "P1") (pin "1") (pinfunction "1_1") (pintype "passive"))
      (node (ref "P2") (pin "1") (pinfunction "1_1") (pintype "passive"))
      (node (ref "P3") (pin "1") (pinfunction "1_1") (pintype "passive"))
      (node (ref "P4") (pin "1") (pinfunction "1_1") (pintype "passive"))
      (node (ref "P5") (pin "1") (pinfunction "1_1") (pintype "passive"))
      (node (ref "P6") (pin "1") (pinfunction "1_1") (pintype "passive"))
      (node (ref "P7") (pin "1") (pinfunction "1_1") (pintype "passive"))
      (node (ref "SH1") (pin "2") (pinfunction "P$2_2") (pintype "bidirectional"))
    )
    (net (code "24") (name "/PROG") (class "Default")
      (node (ref "R7") (pin "P$1") (pinfunction "P$1_P$1") (pintype "passive"))
      (node (ref "R8") (pin "P$2") (pinfunction "P$2_P$2") (pintype "passive"))
      (node (ref "U3") (pin "3") (pinfunction "PROG_3") (pintype "input"))
    )
    (net (code "25") (name "/PWR_LED") (class "Default")
      (node (ref "R15") (pin "P$2") (pinfunction "P$2_P$2") (pintype "passive"))
      (node (ref "U2") (pin "25") (pinfunction "PB12_25") (pintype "bidirectional"))
    )
    (net (code "26") (name "/PWR_SW") (class "Default")
      (node (ref "D2") (pin "ANODE") (pinfunction "ANODE_ANODE") (pintype "bidirectional"))
      (node (ref "J2") (pin "3") (pinfunction "3_3") (pintype "passive"))
      (node (ref "R3") (pin "P$2") (pinfunction "P$2_P$2") (pintype "passive"))
    )
    (net (code "27") (name "/SNS_PWR_SW") (class "Default")
      (node (ref "D6") (pin "CATHODE") (pinfunction "CATHODE_CATHODE") (pintype "bidirectional"))
      (node (ref "R17") (pin "P$1") (pinfunction "P$1_P$1") (pintype "passive"))
      (node (ref "R3") (pin "P$1") (pinfunction "P$1_P$1") (pintype "passive"))
      (node (ref "U2") (pin "10") (pinfunction "PA2_10") (pintype "bidirectional"))
    )
    (net (code "28") (name "/SWCLK") (class "Default")
      (node (ref "J1") (pin "5") (pinfunction "5_5") (pintype "passive"))
      (node (ref "U2") (pin "37") (pinfunction "PA14_37") (pintype "bidirectional"))
    )
    (net (code "29") (name "/SWDIO") (class "Default")
      (node (ref "J1") (pin "3") (pinfunction "3_3") (pintype "passive"))
      (node (ref "U2") (pin "36") (pinfunction "PA13_36") (pintype "bidirectional"))
    )
    (net (code "30") (name "/TIMER") (class "Default")
      (node (ref "C14") (pin "P$1") (pinfunction "P$1_P$1") (pintype "passive"))
      (node (ref "DB_TIMER") (pin "P$1") (pinfunction "P$1_P$1") (pintype "bidirectional"))
      (node (ref "U2") (pin "24") (pinfunction "PB11_24") (pintype "bidirectional"))
      (node (ref "U3") (pin "4") (pinfunction "TIMER_4") (pintype "bidirectional"))
    )
    (net (code "31") (name "/TPS_EN") (class "Default")
      (node (ref "DB_LEN") (pin "P$1") (pinfunction "P$1_P$1") (pintype "bidirectional"))
      (node (ref "Q4") (pin "P$1") (pinfunction "GATE_P$1") (pintype "bidirectional"))
      (node (ref "R16") (pin "P$2") (pinfunction "P$2_P$2") (pintype "passive"))
      (node (ref "U2") (pin "3") (pinfunction "PC14-OSC32_IN_3") (pintype "bidirectional"))
    )
    (net (code "32") (name "/VIN_SAMP") (class "Default")
      (node (ref "C18") (pin "P$1") (pinfunction "P$1_P$1") (pintype "passive"))
      (node (ref "R11") (pin "P$1") (pinfunction "P$1_P$1") (pintype "passive"))
      (node (ref "R12") (pin "P$2") (pinfunction "P$2_P$2") (pintype "passive"))
      (node (ref "U2") (pin "27") (pinfunction "PB14_27") (pintype "bidirectional"))
    )
    (net (code "33") (name "/VREF") (class "Default")
      (node (ref "R7") (pin "P$2") (pinfunction "P$2_P$2") (pintype "passive"))
      (node (ref "U3") (pin "2") (pinfunction "VREF_2") (pintype "output"))
    )
    (net (code "34") (name "/VSENSE") (class "Default")
      (node (ref "Q1") (pin "2") (pinfunction "D_2") (pintype "passive"))
      (node (ref "Q2") (pin "2") (pinfunction "D_2") (pintype "passive"))
      (node (ref "Q3") (pin "2") (pinfunction "D_2") (pintype "passive"))
      (node (ref "R4") (pin "2") (pinfunction "2_2") (pintype "passive"))
    )
    (net (code "35") (name "/VSENSE_HIGH") (class "Default")
      (node (ref "R4") (pin "3") (pinfunction "S1_3") (pintype "passive"))
      (node (ref "U3") (pin "10") (pinfunction "VCC_10") (pintype "power_in"))
      (node (ref "U5") (pin "7") (pinfunction "VS+_7") (pintype "input"))
    )
    (net (code "36") (name "/VSENSE_LOW") (class "Default")
      (node (ref "R4") (pin "4") (pinfunction "S2_4") (pintype "passive"))
      (node (ref "U3") (pin "9") (pinfunction "SENSE_9") (pintype "input"))
      (node (ref "U5") (pin "2") (pinfunction "VS-_2") (pintype "input"))
    )
    (net (code "37") (name "/VSW") (class "Default")
      (node (ref "L1") (pin "2") (pinfunction "2_2") (pintype "passive"))
      (node (ref "U1") (pin "8") (pinfunction "LX_8") (pintype "passive"))
    )
    (net (code "38") (name "/VSWITCHED") (class "Default")
      (node (ref "C15") (pin "P$1") (pinfunction "P$1_P$1") (pintype "passive"))
      (node (ref "D8") (pin "3") (pinfunction "CATHODE_3") (pintype "passive"))
      (node (ref "DB_VSW") (pin "P$1") (pinfunction "P$1_P$1") (pintype "bidirectional"))
      (node (ref "P1") (pin "2") (pinfunction "2_2") (pintype "passive"))
      (node (ref "P2") (pin "2") (pinfunction "2_2") (pintype "passive"))
      (node (ref "P3") (pin "2") (pinfunction "2_2") (pintype "passive"))
      (node (ref "P4") (pin "2") (pinfunction "2_2") (pintype "passive"))
      (node (ref "P5") (pin "2") (pinfunction "2_2") (pintype "passive"))
      (node (ref "P6") (pin "2") (pinfunction "2_2") (pintype "passive"))
      (node (ref "Q1") (pin "3") (pinfunction "S_3") (pintype "passive"))
      (node (ref "Q2") (pin "3") (pinfunction "S_3") (pintype "passive"))
      (node (ref "Q3") (pin "3") (pinfunction "S_3") (pintype "passive"))
      (node (ref "R13") (pin "P$2") (pinfunction "P$2_P$2") (pintype "passive"))
      (node (ref "U3") (pin "7") (pinfunction "OUT_7") (pintype "input"))
    )
    (net (code "39") (name "/VSWITCHED_SAMP") (class "Default")
      (node (ref "C19") (pin "P$1") (pinfunction "P$1_P$1") (pintype "passive"))
      (node (ref "R13") (pin "P$1") (pinfunction "P$1_P$1") (pintype "passive"))
      (node (ref "R14") (pin "P$2") (pinfunction "P$2_P$2") (pintype "passive"))
      (node (ref "U2") (pin "15") (pinfunction "PA7_15") (pintype "bidirectional"))
    )
    (net (code "40") (name "GND") (class "Default")
      (node (ref "C1") (pin "P$2") (pinfunction "P$2_P$2") (pintype "passive"))
      (node (ref "C10") (pin "P$2") (pinfunction "P$2_P$2") (pintype "passive"))
      (node (ref "C11") (pin "P$2") (pinfunction "P$2_P$2") (pintype "passive"))
      (node (ref "C12") (pin "P$2") (pinfunction "P$2_P$2") (pintype "passive"))
      (node (ref "C13") (pin "P$2") (pinfunction "P$2_P$2") (pintype "passive"))
      (node (ref "C14") (pin "P$2") (pinfunction "P$2_P$2") (pintype "passive"))
      (node (ref "C16") (pin "P$2") (pinfunction "P$2_P$2") (pintype "passive"))
      (node (ref "C18") (pin "P$2") (pinfunction "P$2_P$2") (pintype "passive"))
      (node (ref "C19") (pin "P$2") (pinfunction "P$2_P$2") (pintype "passive"))
      (node (ref "C20") (pin "P$2") (pinfunction "P$2_P$2") (pintype "passive"))
      (node (ref "C21") (pin "P$2") (pinfunction "P$2_P$2") (pintype "passive"))
      (node (ref "C23") (pin "P$2") (pinfunction "P$2_P$2") (pintype "passive"))
      (node (ref "C24") (pin "P$2") (pinfunction "P$2_P$2") (pintype "passive"))
      (node (ref "C25") (pin "P$2") (pinfunction "P$2_P$2") (pintype "passive"))
      (node (ref "C26") (pin "P$2") (pinfunction "P$2_P$2") (pintype "passive"))
      (node (ref "C28") (pin "P$2") (pinfunction "P$2_P$2") (pintype "passive"))
      (node (ref "C3") (pin "P$2") (pinfunction "P$2_P$2") (pintype "passive"))
      (node (ref "C4") (pin "P$2") (pinfunction "P$2_P$2") (pintype "passive"))
      (node (ref "C5") (pin "P$2") (pinfunction "P$2_P$2") (pintype "passive"))
      (node (ref "C6") (pin "P$2") (pinfunction "P$2_P$2") (pintype "passive"))
      (node (ref "C7") (pin "P$2") (pinfunction "P$2_P$2") (pintype "passive"))
      (node (ref "C8") (pin "P$2") (pinfunction "P$2_P$2") (pintype "passive"))
      (node (ref "C9") (pin "P$2") (pinfunction "P$2_P$2") (pintype "passive"))
      (node (ref "CAN1") (pin "3") (pinfunction "3_3") (pintype "passive"))
      (node (ref "CAN2") (pin "3") (pinfunction "3_3") (pintype "passive"))
      (node (ref "D6") (pin "ANODE") (pinfunction "ANODE_ANODE") (pintype "bidirectional"))
      (node (ref "DB_G") (pin "P$1") (pinfunction "P$1_P$1") (pintype "bidirectional"))
      (node (ref "J1") (pin "4") (pinfunction "4_4") (pintype "passive"))
      (node (ref "J2") (pin "2") (pinfunction "2_2") (pintype "passive"))
      (node (ref "J3") (pin "5") (pinfunction "5_5") (pintype "passive"))
      (node (ref "Q4") (pin "P$2") (pinfunction "SOURCE_P$2") (pintype "bidirectional"))
      (node (ref "R1") (pin "P$2") (pinfunction "P$2_P$2") (pintype "passive"))
      (node (ref "R12") (pin "P$1") (pinfunction "P$1_P$1") (pintype "passive"))
      (node (ref "R14") (pin "P$1") (pinfunction "P$1_P$1") (pintype "passive"))
      (node (ref "R16") (pin "P$1") (pinfunction "P$1_P$1") (pintype "passive"))
      (node (ref "R17") (pin "P$2") (pinfunction "P$2_P$2") (pintype "passive"))
      (node (ref "R18") (pin "P$1") (pinfunction "P$1_P$1") (pintype "passive"))
      (node (ref "R2") (pin "P$1") (pinfunction "P$1_P$1") (pintype "passive"))
      (node (ref "R29") (pin "P$2") (pinfunction "P$2_P$2") (pintype "passive"))
      (node (ref "R30") (pin "P$2") (pinfunction "P$2_P$2") (pintype "passive"))
      (node (ref "R8") (pin "P$1") (pinfunction "P$1_P$1") (pintype "passive"))
      (node (ref "SH1") (pin "1") (pinfunction "P$1_1") (pintype "bidirectional"))
      (node (ref "U1") (pin "7") (pinfunction "GND_7") (pintype "power_in"))
      (node (ref "U2") (pin "29") (pinfunction "PC6_29") (pintype "bidirectional"))
      (node (ref "U2") (pin "38") (pinfunction "PA15_38") (pintype "bidirectional"))
      (node (ref "U2") (pin "49") (pinfunction "THERMALPAD_49") (pintype "bidirectional"))
      (node (ref "U3") (pin "5") (pinfunction "GND_5") (pintype "power_in"))
      (node (ref "U4") (pin "2") (pinfunction "GND_2") (pintype "power_in"))
      (node (ref "U4") (pin "8") (pinfunction "STB_8") (pintype "input"))
      (node (ref "U5") (pin "4") (pinfunction "VEE_4") (pintype "power_in"))
      (node (ref "U6") (pin "3") (pinfunction "GND_3") (pintype "power_in"))
      (node (ref "U7") (pin "2") (pinfunction "GND_2") (pintype "bidirectional"))
    )
    (net (code "41") (name "Net-(C13-PadP$1)") (class "Default")
      (node (ref "C13") (pin "P$1") (pinfunction "P$1_P$1") (pintype "passive"))
      (node (ref "R6") (pin "P$1") (pinfunction "P$1_P$1") (pintype "passive"))
    )
    (net (code "42") (name "Net-(D4-PadANODE)") (class "Default")
      (node (ref "D4") (pin "ANODE") (pinfunction "ANODE_ANODE") (pintype "power_in"))
      (node (ref "R9") (pin "P$1") (pinfunction "P$1_P$1") (pintype "passive"))
    )
    (net (code "43") (name "Net-(D5-PadANODE)") (class "Default")
      (node (ref "D5") (pin "ANODE") (pinfunction "ANODE_ANODE") (pintype "power_in"))
      (node (ref "R10") (pin "P$1") (pinfunction "P$1_P$1") (pintype "passive"))
    )
    (net (code "44") (name "Net-(J2-Pad1)") (class "Default")
      (node (ref "J2") (pin "1") (pinfunction "1_1") (pintype "passive"))
      (node (ref "R15") (pin "P$1") (pinfunction "P$1_P$1") (pintype "passive"))
    )
    (net (code "45") (name "Net-(Q4-DRAIN)") (class "Default")
      (node (ref "Q4") (pin "P$3") (pinfunction "DRAIN_P$3") (pintype "bidirectional"))
      (node (ref "R22") (pin "P$1") (pinfunction "P$1_P$1") (pintype "passive"))
    )
    (net (code "46") (name "Net-(Q5-DRAIN)") (class "Default")
      (node (ref "Q5") (pin "P$3") (pinfunction "DRAIN_P$3") (pintype "bidirectional"))
      (node (ref "R19") (pin "P$2") (pinfunction "P$2_P$2") (pintype "passive"))
    )
    (net (code "47") (name "Net-(Q5-GATE)") (class "Default")
      (node (ref "Q5") (pin "P$1") (pinfunction "GATE_P$1") (pintype "bidirectional"))
      (node (ref "R20") (pin "P$1") (pinfunction "P$1_P$1") (pintype "passive"))
      (node (ref "R22") (pin "P$2") (pinfunction "P$2_P$2") (pintype "passive"))
    )
    (net (code "48") (name "Net-(U$3-1)") (class "Default")
      (node (ref "C1") (pin "P$1") (pinfunction "P$1_P$1") (pintype "passive"))
      (node (ref "R1") (pin "P$1") (pinfunction "P$1_P$1") (pintype "passive"))
      (node (ref "U$3") (pin "P$1") (pinfunction "1_P$1") (pintype "passive"))
    )
    (net (code "49") (name "Net-(U1-MODE)") (class "Default")
      (node (ref "R30") (pin "P$1") (pinfunction "P$1_P$1") (pintype "passive"))
      (node (ref "U1") (pin "5") (pinfunction "MODE_5") (pintype "input"))
    )
    (net (code "50") (name "Net-(U1-VCC)") (class "Default")
      (node (ref "C3") (pin "P$1") (pinfunction "P$1_P$1") (pintype "passive"))
      (node (ref "U1") (pin "3") (pinfunction "VCC_3") (pintype "power_in"))
    )
    (net (code "51") (name "Net-(U2-PA1)") (class "Default")
      (node (ref "R26") (pin "P$1") (pinfunction "P$1_P$1") (pintype "passive"))
      (node (ref "U2") (pin "9") (pinfunction "PA1_9") (pintype "bidirectional"))
    )
    (net (code "52") (name "Net-(U2-PA3)") (class "Default")
      (node (ref "C23") (pin "P$1") (pinfunction "P$1_P$1") (pintype "passive"))
      (node (ref "U2") (pin "11") (pinfunction "PA3_11") (pintype "bidirectional"))
    )
    (net (code "53") (name "Net-(U3-EN)") (class "Default")
      (node (ref "R18") (pin "P$2") (pinfunction "P$2_P$2") (pintype "passive"))
      (node (ref "R19") (pin "P$1") (pinfunction "P$1_P$1") (pintype "passive"))
      (node (ref "U3") (pin "1") (pinfunction "EN_1") (pintype "input"))
    )
    (net (code "54") (name "Net-(U4-SHDN)") (class "Default")
      (node (ref "C26") (pin "P$1") (pinfunction "P$1_P$1") (pintype "passive"))
      (node (ref "R28") (pin "P$2") (pinfunction "P$2_P$2") (pintype "passive"))
      (node (ref "R29") (pin "P$1") (pinfunction "P$1_P$1") (pintype "passive"))
      (node (ref "U4") (pin "5") (pinfunction "SHDN_5") (pintype "input"))
    )
    (net (code "55") (name "Net-(U4-VCC)") (class "Default")
      (node (ref "C21") (pin "P$1") (pinfunction "P$1_P$1") (pintype "passive"))
      (node (ref "C28") (pin "P$1") (pinfunction "P$1_P$1") (pintype "passive"))
      (node (ref "R23") (pin "P$2") (pinfunction "P$2_P$2") (pintype "passive"))
      (node (ref "R27") (pin "P$2") (pinfunction "P$2_P$2") (pintype "passive"))
      (node (ref "U4") (pin "3") (pinfunction "VCC_3") (pintype "power_in"))
    )
    (net (code "56") (name "Net-(U5-FIL+)") (class "Default")
      (node (ref "C17") (pin "P$2") (pinfunction "P$2_P$2") (pintype "passive"))
      (node (ref "U5") (pin "8") (pinfunction "FIL+_8") (pintype "passive"))
    )
    (net (code "57") (name "Net-(U5-FIL-)") (class "Default")
      (node (ref "C17") (pin "P$1") (pinfunction "P$1_P$1") (pintype "passive"))
      (node (ref "U5") (pin "1") (pinfunction "FIL-_1") (pintype "passive"))
    )
    (net (code "58") (name "Net-(U5-VBIAS)") (class "Default")
      (node (ref "R24") (pin "P$2") (pinfunction "P$2_P$2") (pintype "passive"))
      (node (ref "U5") (pin "6") (pinfunction "VBIAS_6") (pintype "output"))
    )
    (net (code "59") (name "Net-(U7-LX)") (class "Default")
      (node (ref "L2") (pin "2") (pinfunction "2_2") (pintype "passive"))
      (node (ref "U7") (pin "5") (pinfunction "LX_5") (pintype "bidirectional"))
    )
    (net (code "60") (name "VCC") (class "Default")
      (node (ref "C10") (pin "P$1") (pinfunction "P$1_P$1") (pintype "passive"))
      (node (ref "C11") (pin "P$1") (pinfunction "P$1_P$1") (pintype "passive"))
      (node (ref "C16") (pin "P$1") (pinfunction "P$1_P$1") (pintype "passive"))
      (node (ref "C25") (pin "P$1") (pinfunction "P$1_P$1") (pintype "passive"))
      (node (ref "C6") (pin "P$1") (pinfunction "P$1_P$1") (pintype "passive"))
      (node (ref "C7") (pin "P$1") (pinfunction "P$1_P$1") (pintype "passive"))
      (node (ref "C8") (pin "P$1") (pinfunction "P$1_P$1") (pintype "passive"))
      (node (ref "C9") (pin "P$1") (pinfunction "P$1_P$1") (pintype "passive"))
      (node (ref "DB_3") (pin "P$1") (pinfunction "P$1_P$1") (pintype "bidirectional"))
      (node (ref "J1") (pin "6") (pinfunction "6_6") (pintype "passive"))
      (node (ref "J3") (pin "1") (pinfunction "1_1") (pintype "passive"))
      (node (ref "L2") (pin "1") (pinfunction "1_1") (pintype "passive"))
      (node (ref "R10") (pin "P$2") (pinfunction "P$2_P$2") (pintype "passive"))
      (node (ref "R21") (pin "P$2") (pinfunction "P$2_P$2") (pintype "passive"))
      (node (ref "R27") (pin "P$1") (pinfunction "P$1_P$1") (pintype "passive"))
      (node (ref "R28") (pin "P$1") (pinfunction "P$1_P$1") (pintype "passive"))
      (node (ref "R9") (pin "P$2") (pinfunction "P$2_P$2") (pintype "passive"))
      (node (ref "U2") (pin "1") (pinfunction "VBAT_1") (pintype "bidirectional"))
      (node (ref "U2") (pin "20") (pinfunction "VREF+_20") (pintype "bidirectional"))
      (node (ref "U2") (pin "21") (pinfunction "VDDA_21") (pintype "bidirectional"))
      (node (ref "U2") (pin "23") (pinfunction "VDD_1_23") (pintype "bidirectional"))
      (node (ref "U2") (pin "35") (pinfunction "VDD_2_35") (pintype "bidirectional"))
      (node (ref "U2") (pin "48") (pinfunction "VDD_3_48") (pintype "bidirectional"))
      (node (ref "U6") (pin "4") (pinfunction "VCC_4") (pintype "power_in"))
      (node (ref "U7") (pin "4") (pinfunction "VOUT_4") (pintype "bidirectional"))
    )
    (net (code "61") (name "unconnected-(J1-Pad1)") (class "Default")
      (node (ref "J1") (pin "1") (pinfunction "1_1") (pintype "passive"))
    )
    (net (code "62") (name "unconnected-(U$1-1-PadP$1)") (class "Default")
      (node (ref "U$1") (pin "P$1") (pinfunction "1_P$1") (pintype "passive"))
    )
    (net (code "63") (name "unconnected-(U$2-1-PadP$1)") (class "Default")
      (node (ref "U$2") (pin "P$1") (pinfunction "1_P$1") (pintype "passive"))
    )
    (net (code "64") (name "unconnected-(U$4-1-PadP$1)") (class "Default")
      (node (ref "U$4") (pin "P$1") (pinfunction "1_P$1") (pintype "passive"))
    )
    (net (code "65") (name "unconnected-(U1-~{RESET}-Pad6)") (class "Default")
      (node (ref "U1") (pin "6") (pinfunction "~{RESET}_6") (pintype "output"))
    )
    (net (code "66") (name "unconnected-(U2-PA6-Pad14)") (class "Default")
      (node (ref "U2") (pin "14") (pinfunction "PA6_14") (pintype "bidirectional"))
    )
    (net (code "67") (name "unconnected-(U2-PA9-Pad31)") (class "Default")
      (node (ref "U2") (pin "31") (pinfunction "PA9_31") (pintype "bidirectional"))
    )
    (net (code "68") (name "unconnected-(U2-PA10-Pad32)") (class "Default")
      (node (ref "U2") (pin "32") (pinfunction "PA10_32") (pintype "bidirectional"))
    )
    (net (code "69") (name "unconnected-(U2-PB2-Pad19)") (class "Default")
      (node (ref "U2") (pin "19") (pinfunction "PB2_19") (pintype "bidirectional"))
    )
    (net (code "70") (name "unconnected-(U2-PB4-Pad42)") (class "Default")
      (node (ref "U2") (pin "42") (pinfunction "PB4_42") (pintype "bidirectional"))
    )
    (net (code "71") (name "unconnected-(U2-PB5-Pad43)") (class "Default")
      (node (ref "U2") (pin "43") (pinfunction "PB5_43") (pintype "bidirectional"))
    )
    (net (code "72") (name "unconnected-(U2-PB6-Pad44)") (class "Default")
      (node (ref "U2") (pin "44") (pinfunction "PB6_44") (pintype "bidirectional"))
    )
    (net (code "73") (name "unconnected-(U2-PB7-Pad45)") (class "Default")
      (node (ref "U2") (pin "45") (pinfunction "PB7_45") (pintype "bidirectional"))
    )
    (net (code "74") (name "unconnected-(U2-PB8-BOOT0-Pad46)") (class "Default")
      (node (ref "U2") (pin "46") (pinfunction "PB8-BOOT0_46") (pintype "bidirectional"))
    )
    (net (code "75") (name "unconnected-(U2-PB10-Pad22)") (class "Default")
      (node (ref "U2") (pin "22") (pinfunction "PB10_22") (pintype "bidirectional"))
    )
    (net (code "76") (name "unconnected-(U2-PC13-Pad2)") (class "Default")
      (node (ref "U2") (pin "2") (pinfunction "PC13_2") (pintype "bidirectional"))
    )
    (net (code "77") (name "unconnected-(U2-PC15-OSC32_OUT-Pad4)") (class "Default")
      (node (ref "U2") (pin "4") (pinfunction "PC15-OSC32_OUT_4") (pintype "bidirectional"))
    )
    (net (code "78") (name "unconnected-(U2-PF0-OSC_IN-Pad5)") (class "Default")
      (node (ref "U2") (pin "5") (pinfunction "PF0-OSC_IN_5") (pintype "bidirectional"))
    )
    (net (code "79") (name "unconnected-(U2-PF1-OSC_OUT-Pad6)") (class "Default")
      (node (ref "U2") (pin "6") (pinfunction "PF1-OSC_OUT_6") (pintype "bidirectional"))
    )
    (net (code "80") (name "unconnected-(U5-DNC-Pad3)") (class "Default")
      (node (ref "U5") (pin "3") (pinfunction "DNC_3") (pintype "no_connect"))
    )
    (net (code "81") (name "unconnected-(U6-NC-Pad2)") (class "Default")
      (node (ref "U6") (pin "2") (pinfunction "NC_2") (pintype "no_connect"))
    )
  )
)
